# Headers.net
KiCad netlist of a schematic drawn in Altium Designer
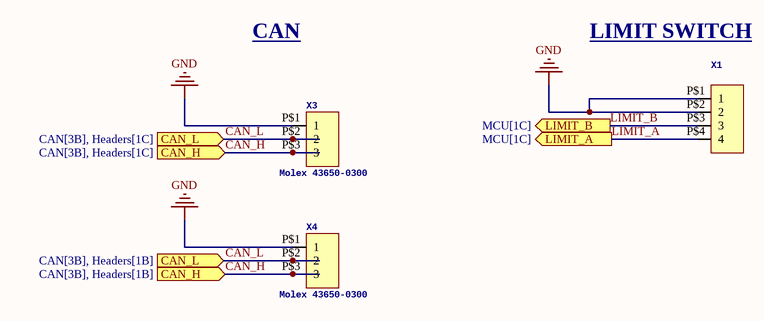
[diagram p0: Headers.SchDoc]

(export (version "E")
  (design (tool "Eeschema 10.0.6"))
  (components
    (comp (ref "X1")
      (value "Molex - Micro-Fit 3.0 Series connector,  3.00mm (0.118\") pitch header, 4 positions.")
      (footprint "43045-0400")
      (libsource (lib "Molex Microfit") (part "HEADER_POS4_?43045-0401"))
    )
    (comp (ref "X3")
      (value "Molex 43650-0300")
      (footprint "43650-0300")
      (libsource (lib "Molex Microfit") (part "Micro-Fit Molex 3 Pin Right Angle"))
    )
    (comp (ref "X4")
      (value "Molex 43650-0300")
      (footprint "43650-0300")
      (libsource (lib "Molex Microfit") (part "Micro-Fit Molex 3 Pin Right Angle"))
    )
  )
  (nets
    (net (code "1") (name "/CAN_H") (class "Default")
      (node (ref "X3") (pin "P$3") (pinfunction "3_P$3") (pintype "passive"))
      (node (ref "X4") (pin "P$3") (pinfunction "3_P$3") (pintype "passive"))
    )
    (net (code "2") (name "/CAN_L") (class "Default")
      (node (ref "X3") (pin "P$2") (pinfunction "2_P$2") (pintype "passive"))
      (node (ref "X4") (pin "P$2") (pinfunction "2_P$2") (pintype "passive"))
    )
    (net (code "3") (name "/LIMIT_A") (class "Default")
      (node (ref "X1") (pin "P$4") (pinfunction "4_P$4") (pintype "passive"))
    )
    (net (code "4") (name "/LIMIT_B") (class "Default")
      (node (ref "X1") (pin "P$3") (pinfunction "3_P$3") (pintype "passive"))
    )
    (net (code "5") (name "GND") (class "Default")
      (node (ref "X1") (pin "P$1") (pinfunction "1_P$1") (pintype "passive"))
      (node (ref "X1") (pin "P$2") (pinfunction "2_P$2") (pintype "passive"))
      (node (ref "X3") (pin "P$1") (pinfunction "1_P$1") (pintype "passive"))
      (node (ref "X4") (pin "P$1") (pinfunction "1_P$1") (pintype "passive"))
    )
  )
)
